# TOP_LAYER.net
KiCad netlist of a schematic drawn in Altium Designer
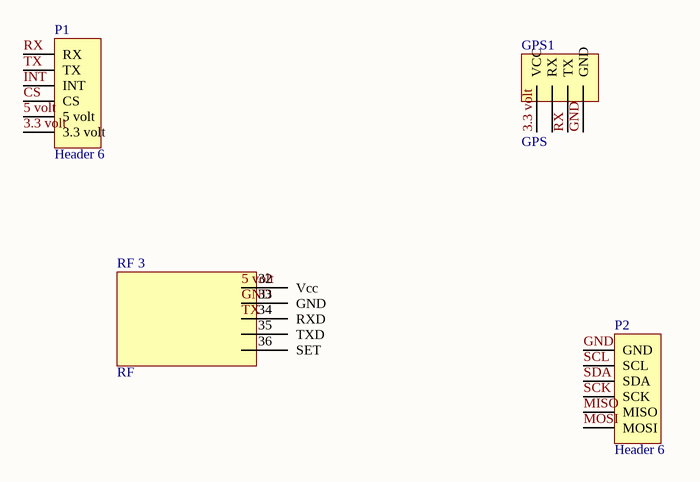
[diagram p0: TOP LAYER.SchDoc]

(export (version "E")
  (design (tool "Eeschema 10.0.6"))
  (components
    (comp (ref "GPS1") (value "GPS") (footprint "GPS") (libsource (lib "GPS") (part "GPS")))
    (comp (ref "P1")
      (value "Header 6")
      (footprint "HDR1X6")
      (description "Header, 6-Pin")
      (fields (field (name "PUBLISHER") "Altium Limited"))
      (libsource (lib "Miscellaneous Connectors") (part "Header 6"))
    )
    (comp (ref "P2")
      (value "Header 6")
      (footprint "HDR1X6")
      (description "Header, 6-Pin")
      (fields (field (name "PUBLISHER") "Altium Limited"))
      (libsource (lib "Miscellaneous Connectors") (part "Header 6"))
    )
    (comp (ref "RF 3") (value "RF") (footprint "RF") (libsource (lib "RF") (part "RF")))
  )
  (nets
    (net (code "1") (name "/3.3 volt") (class "Default")
      (node (ref "GPS1") (pin "12") (pinfunction "VCC_12") (pintype "passive"))
      (node (ref "P1") (pin "6") (pinfunction "3.3_volt_6") (pintype "passive"))
    )
    (net (code "2") (name "/5 volt") (class "Default")
      (node (ref "P1") (pin "5") (pinfunction "5_volt_5") (pintype "passive"))
      (node (ref "RF 3") (pin "32") (pinfunction "Vcc_32") (pintype "passive"))
    )
    (net (code "3") (name "/CS") (class "Default")
      (node (ref "P1") (pin "4") (pinfunction "CS_4") (pintype "passive"))
    )
    (net (code "4") (name "/GND") (class "Default")
      (node (ref "GPS1") (pin "15") (pinfunction "GND_15") (pintype "passive"))
      (node (ref "P2") (pin "1") (pinfunction "RX_1") (pintype "passive"))
      (node (ref "RF 3") (pin "33") (pinfunction "GND_33") (pintype "passive"))
    )
    (net (code "5") (name "/INT") (class "Default")
      (node (ref "P1") (pin "3") (pinfunction "INT_3") (pintype "passive"))
    )
    (net (code "6") (name "/MISO") (class "Default")
      (node (ref "P2") (pin "5") (pinfunction "5_volt_5") (pintype "passive"))
    )
    (net (code "7") (name "/MOSI") (class "Default")
      (node (ref "P2") (pin "6") (pinfunction "3.3_volt_6") (pintype "passive"))
    )
    (net (code "8") (name "/RX") (class "Default")
      (node (ref "GPS1") (pin "14") (pinfunction "TX_14") (pintype "passive"))
      (node (ref "P1") (pin "1") (pinfunction "RX_1") (pintype "passive"))
    )
    (net (code "9") (name "/SCK") (class "Default")
      (node (ref "P2") (pin "4") (pinfunction "CS_4") (pintype "passive"))
    )
    (net (code "10") (name "/SCL") (class "Default")
      (node (ref "P2") (pin "2") (pinfunction "TX_2") (pintype "passive"))
    )
    (net (code "11") (name "/SDA") (class "Default")
      (node (ref "P2") (pin "3") (pinfunction "INT_3") (pintype "passive"))
    )
    (net (code "12") (name "/TX") (class "Default")
      (node (ref "P1") (pin "2") (pinfunction "TX_2") (pintype "passive"))
      (node (ref "RF 3") (pin "34") (pinfunction "RXD_34") (pintype "passive"))
    )
    (net (code "13") (name "unconnected-(GPS1-RX-Pad13)") (class "Default")
      (node (ref "GPS1") (pin "13") (pinfunction "RX_13") (pintype "passive"))
    )
    (net (code "14") (name "unconnected-(RF 3-SET-Pad36)") (class "Default")
      (node (ref "RF 3") (pin "36") (pinfunction "SET_36") (pintype "passive"))
    )
    (net (code "15") (name "unconnected-(RF 3-TXD-Pad35)") (class "Default")
      (node (ref "RF 3") (pin "35") (pinfunction "TXD_35") (pintype "passive"))
    )
  )
)
